# ATTinyAmpDriver.net
KiCad netlist of a schematic drawn in EAGLE
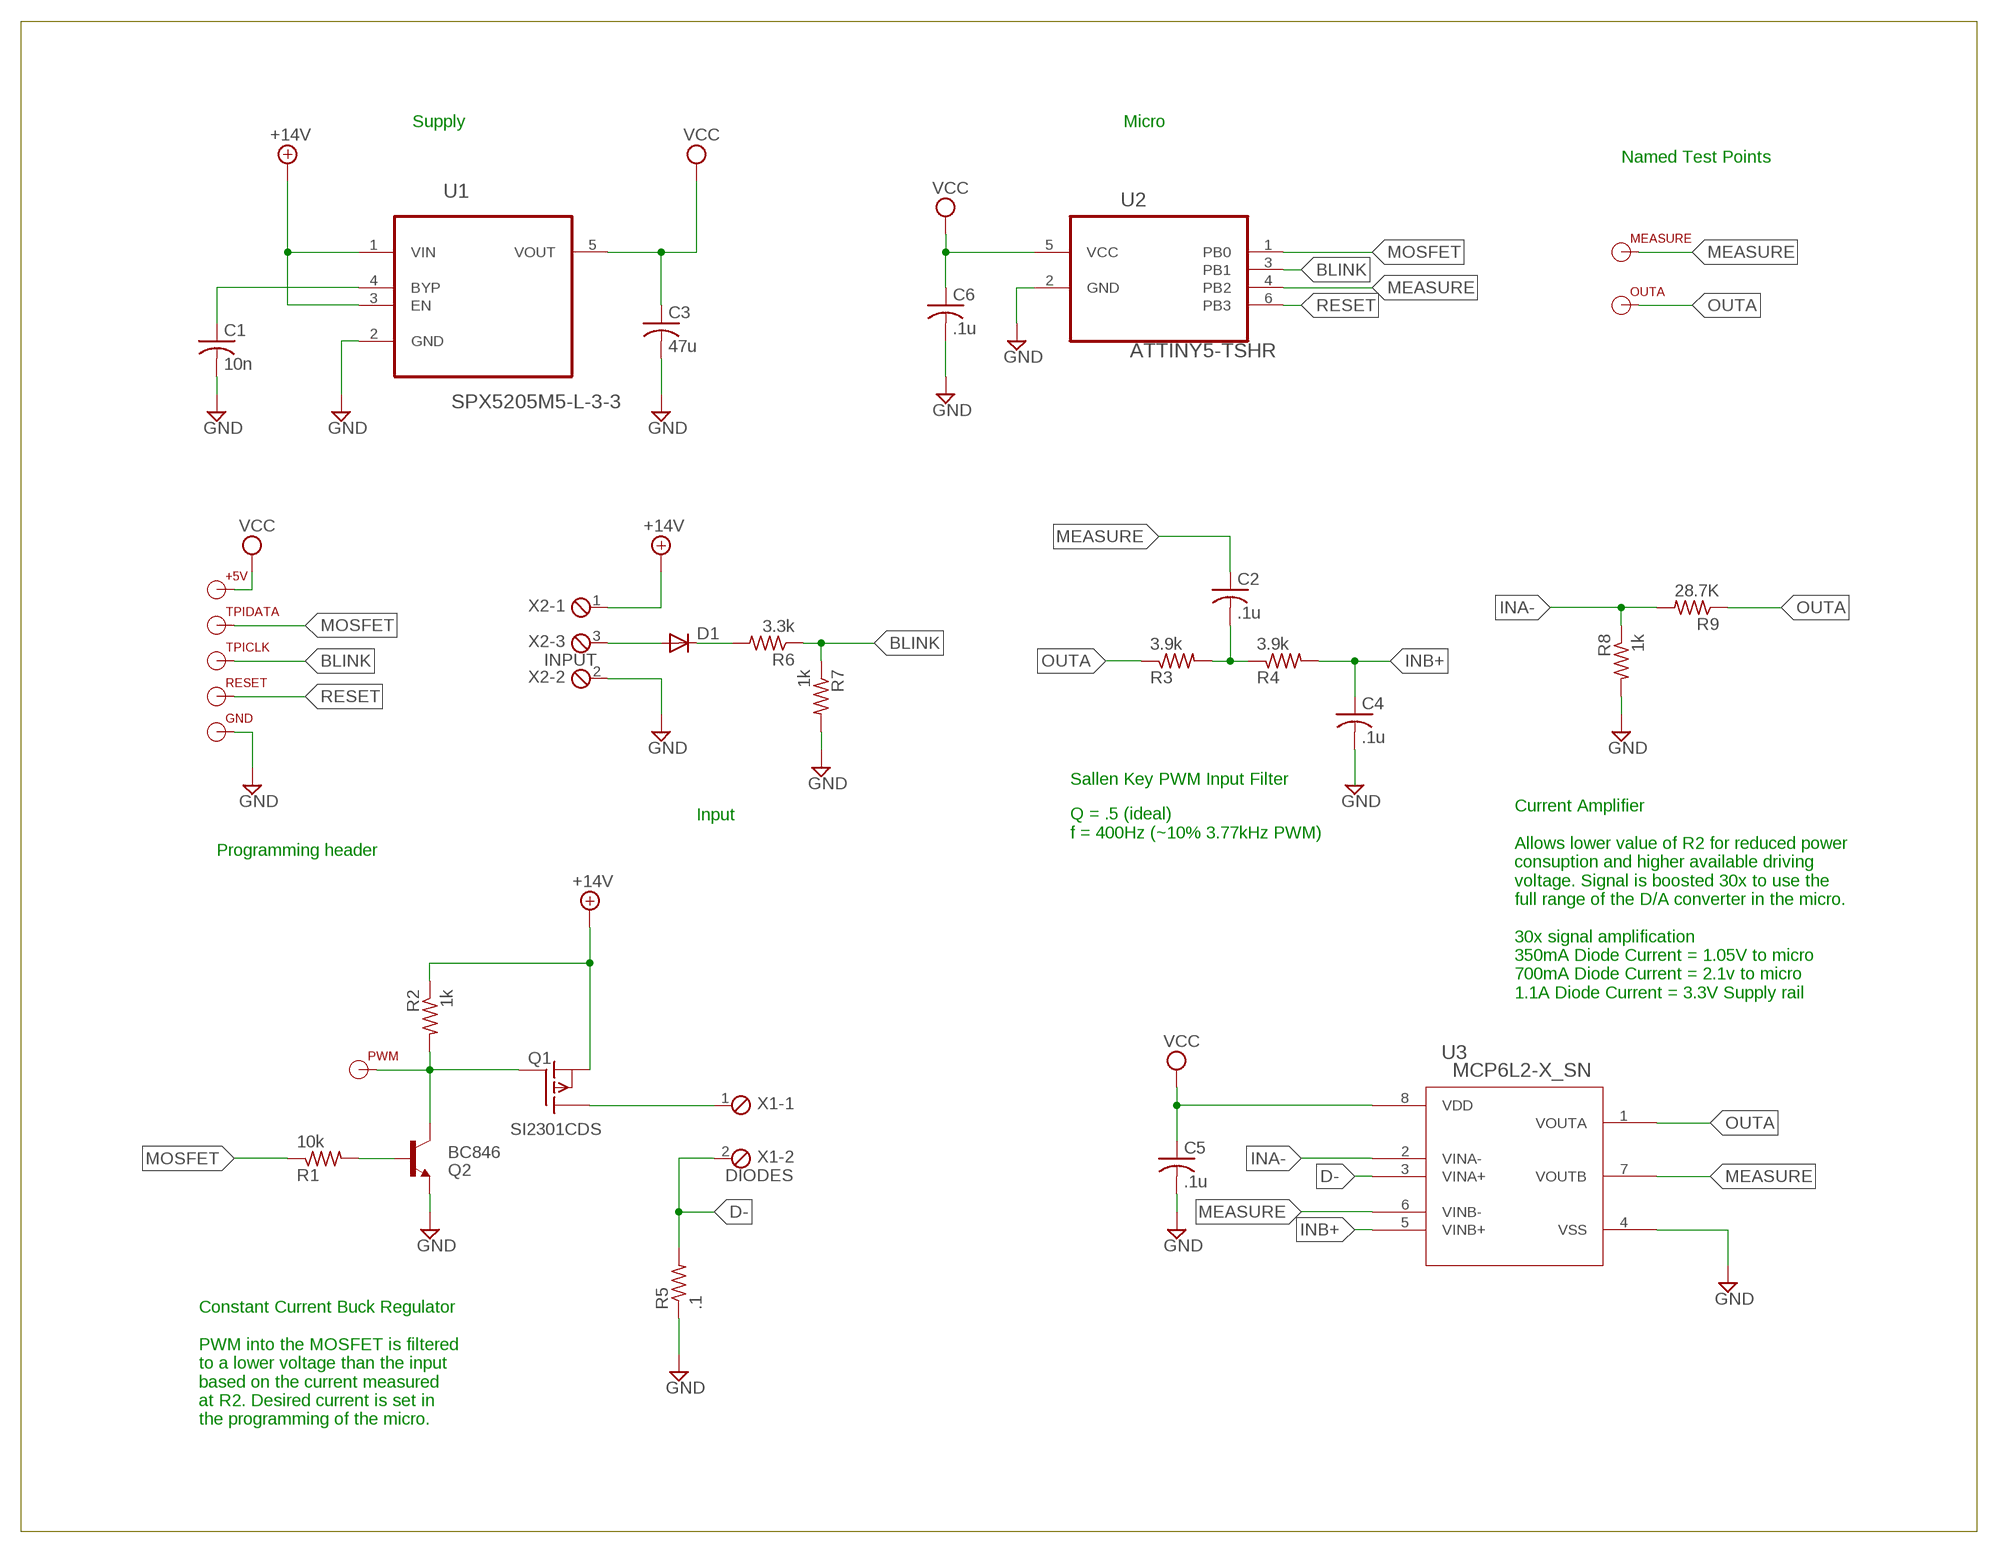
[diagram p0: schematic, sheet 1]

(export (version "E")
  (design (tool "Eeschema 10.0.6"))
  (components
    (comp (ref "+5V")
      (value "TPI")
      (footprint "eagle-import:TPI_PAD")
      (libsource (lib "eagle-import") (part "TPI"))
    )
    (comp (ref "C1")
      (value "10n")
      (footprint "eagle-import:C0603")
      (libsource (lib "eagle-import") (part "C-USC0603"))
    )
    (comp (ref "C2")
      (value ".1u")
      (footprint "eagle-import:C0603")
      (libsource (lib "eagle-import") (part "C-USC0603"))
    )
    (comp (ref "C3")
      (value "47u")
      (footprint "eagle-import:C1206")
      (libsource (lib "eagle-import") (part "C-USC1206"))
    )
    (comp (ref "C4")
      (value ".1u")
      (footprint "eagle-import:C0603")
      (libsource (lib "eagle-import") (part "C-USC0603"))
    )
    (comp (ref "C5")
      (value ".1u")
      (footprint "eagle-import:C0603")
      (libsource (lib "eagle-import") (part "C-USC0603"))
    )
    (comp (ref "C6")
      (value ".1u")
      (footprint "eagle-import:C0603")
      (libsource (lib "eagle-import") (part "C-USC0603"))
    )
    (comp (ref "D1")
      (value "DIODE_0603")
      (footprint "eagle-import:D0603")
      (libsource (lib "eagle-import") (part "DIODE_0603"))
    )
    (comp (ref "GND")
      (value "TPI")
      (footprint "eagle-import:TPI_PAD")
      (libsource (lib "eagle-import") (part "TPI"))
    )
    (comp (ref "MEASURE")
      (value "TPI")
      (footprint "eagle-import:TPI_PAD")
      (libsource (lib "eagle-import") (part "TPI"))
    )
    (comp (ref "OUTA")
      (value "TPI")
      (footprint "eagle-import:TPI_PAD")
      (libsource (lib "eagle-import") (part "TPI"))
    )
    (comp (ref "PWM")
      (value "TPI")
      (footprint "eagle-import:TPI_PAD")
      (libsource (lib "eagle-import") (part "TPI"))
    )
    (comp (ref "Q1")
      (value "SI2301CDS")
      (footprint "eagle-import:SOT-23_POWER")
      (libsource (lib "eagle-import") (part "SI2301CDS"))
    )
    (comp (ref "Q2")
      (value "BC846")
      (footprint "eagle-import:SOT23")
      (libsource (lib "eagle-import") (part "BC846"))
    )
    (comp (ref "R1")
      (value "10k")
      (footprint "eagle-import:R0603")
      (libsource (lib "eagle-import") (part "R-US_R0603"))
    )
    (comp (ref "R2")
      (value "1k")
      (footprint "eagle-import:R0603")
      (libsource (lib "eagle-import") (part "R-US_R0603"))
    )
    (comp (ref "R3")
      (value "3.9k")
      (footprint "eagle-import:R0603")
      (libsource (lib "eagle-import") (part "R-US_R0603"))
    )
    (comp (ref "R4")
      (value "3.9k")
      (footprint "eagle-import:R0603")
      (libsource (lib "eagle-import") (part "R-US_R0603"))
    )
    (comp (ref "R5")
      (value ".1")
      (footprint "eagle-import:R1206")
      (libsource (lib "eagle-import") (part "R-US_R1206"))
    )
    (comp (ref "R6")
      (value "3.3k")
      (footprint "eagle-import:R0603")
      (libsource (lib "eagle-import") (part "R-US_R0603"))
    )
    (comp (ref "R7")
      (value "1k")
      (footprint "eagle-import:R0603")
      (libsource (lib "eagle-import") (part "R-US_R0603"))
    )
    (comp (ref "R8")
      (value "1k")
      (footprint "eagle-import:R0603")
      (libsource (lib "eagle-import") (part "R-US_R0603"))
    )
    (comp (ref "R9")
      (value "28.7K")
      (footprint "eagle-import:R0603")
      (libsource (lib "eagle-import") (part "R-US_R0603"))
    )
    (comp (ref "RESET")
      (value "TPI")
      (footprint "eagle-import:TPI_PAD")
      (libsource (lib "eagle-import") (part "TPI"))
    )
    (comp (ref "TPICLK")
      (value "TPI")
      (footprint "eagle-import:TPI_PAD")
      (libsource (lib "eagle-import") (part "TPI"))
    )
    (comp (ref "TPIDATA")
      (value "TPI")
      (footprint "eagle-import:TPI_PAD")
      (libsource (lib "eagle-import") (part "TPI"))
    )
    (comp (ref "U1")
      (value "SPX5205M5-L-3-3")
      (footprint "eagle-import:SOT95P280X145-5N")
      (libsource (lib "eagle-import") (part "SPX5205M5-L-3-3"))
    )
    (comp (ref "U2")
      (value "ATTINY5-TSHR")
      (footprint "eagle-import:SOT95P280X145-6N")
      (libsource (lib "eagle-import") (part "ATTINY5-TSHR"))
    )
    (comp (ref "U3")
      (value "MCP6L2-X_SN")
      (footprint "eagle-import:SOIC8-N_MC")
      (libsource (lib "eagle-import") (part "MCP6L2-X_SN"))
    )
    (comp (ref "X1")
      (value "DIODES")
      (footprint "eagle-import:2POL254")
      (libsource (lib "eagle-import") (part "MPT2"))
    )
    (comp (ref "X2")
      (value "INPUT")
      (footprint "eagle-import:3POL254")
      (libsource (lib "eagle-import") (part "MPT3"))
    )
  )
  (nets
    (net (code "1") (name "+14V") (class "Default")
      (node (ref "Q1") (pin "P$2") (pinfunction "S_P$2") (pintype "passive"))
      (node (ref "R2") (pin "1") (pinfunction "1_1") (pintype "passive"))
      (node (ref "U1") (pin "1") (pinfunction "VIN_1") (pintype "power_in"))
      (node (ref "U1") (pin "3") (pinfunction "EN_3") (pintype "input"))
      (node (ref "X2") (pin "1") (pinfunction "1_1") (pintype "passive"))
    )
    (net (code "2") (name "BLINK") (class "Default")
      (node (ref "R6") (pin "1") (pinfunction "1_1") (pintype "passive"))
      (node (ref "R7") (pin "1") (pinfunction "1_1") (pintype "passive"))
      (node (ref "TPICLK") (pin "P$1") (pinfunction "TPI_PIN_P$1") (pintype "bidirectional"))
      (node (ref "U2") (pin "3") (pinfunction "PB1_3") (pintype "bidirectional"))
    )
    (net (code "3") (name "D-") (class "Default")
      (node (ref "R5") (pin "2") (pinfunction "2_2") (pintype "passive"))
      (node (ref "U3") (pin "3") (pinfunction "VINA+_3") (pintype "passive"))
      (node (ref "X1") (pin "2") (pinfunction "1_2") (pintype "passive"))
    )
    (net (code "4") (name "GND") (class "Default")
      (node (ref "C1") (pin "2") (pinfunction "2_2") (pintype "passive"))
      (node (ref "C3") (pin "2") (pinfunction "2_2") (pintype "passive"))
      (node (ref "C4") (pin "2") (pinfunction "2_2") (pintype "passive"))
      (node (ref "C5") (pin "2") (pinfunction "2_2") (pintype "passive"))
      (node (ref "C6") (pin "2") (pinfunction "2_2") (pintype "passive"))
      (node (ref "GND") (pin "P$1") (pinfunction "TPI_PIN_P$1") (pintype "bidirectional"))
      (node (ref "Q2") (pin "2") (pinfunction "E_2") (pintype "passive"))
      (node (ref "R5") (pin "1") (pinfunction "1_1") (pintype "passive"))
      (node (ref "R7") (pin "2") (pinfunction "2_2") (pintype "passive"))
      (node (ref "R8") (pin "2") (pinfunction "2_2") (pintype "passive"))
      (node (ref "U1") (pin "2") (pinfunction "GND_2") (pintype "passive"))
      (node (ref "U2") (pin "2") (pinfunction "GND_2") (pintype "passive"))
      (node (ref "U3") (pin "4") (pinfunction "VSS_4") (pintype "passive"))
      (node (ref "X2") (pin "2") (pinfunction "1_2") (pintype "passive"))
    )
    (net (code "5") (name "INA-") (class "Default")
      (node (ref "R8") (pin "1") (pinfunction "1_1") (pintype "passive"))
      (node (ref "R9") (pin "2") (pinfunction "2_2") (pintype "passive"))
      (node (ref "U3") (pin "2") (pinfunction "VINA-_2") (pintype "passive"))
    )
    (net (code "6") (name "INB+") (class "Default")
      (node (ref "C4") (pin "1") (pinfunction "1_1") (pintype "passive"))
      (node (ref "R4") (pin "2") (pinfunction "2_2") (pintype "passive"))
      (node (ref "U3") (pin "5") (pinfunction "VINB+_5") (pintype "passive"))
    )
    (net (code "7") (name "MEASURE") (class "Default")
      (node (ref "C2") (pin "1") (pinfunction "1_1") (pintype "passive"))
      (node (ref "MEASURE") (pin "P$1") (pinfunction "TPI_PIN_P$1") (pintype "bidirectional"))
      (node (ref "U2") (pin "4") (pinfunction "PB2_4") (pintype "bidirectional"))
      (node (ref "U3") (pin "6") (pinfunction "VINB-_6") (pintype "passive"))
      (node (ref "U3") (pin "7") (pinfunction "VOUTB_7") (pintype "passive"))
    )
    (net (code "8") (name "MOSFET") (class "Default")
      (node (ref "R1") (pin "1") (pinfunction "1_1") (pintype "passive"))
      (node (ref "TPIDATA") (pin "P$1") (pinfunction "TPI_PIN_P$1") (pintype "bidirectional"))
      (node (ref "U2") (pin "1") (pinfunction "PB0_1") (pintype "bidirectional"))
    )
    (net (code "9") (name "Net-(C2-Pad2)") (class "Default")
      (node (ref "C2") (pin "2") (pinfunction "2_2") (pintype "passive"))
      (node (ref "R3") (pin "2") (pinfunction "2_2") (pintype "passive"))
      (node (ref "R4") (pin "1") (pinfunction "1_1") (pintype "passive"))
    )
    (net (code "10") (name "Net-(D1-A)") (class "Default")
      (node (ref "D1") (pin "1A") (pinfunction "A_1A") (pintype "passive"))
      (node (ref "X2") (pin "3") (pinfunction "1_3") (pintype "passive"))
    )
    (net (code "11") (name "Net-(D1-C)") (class "Default")
      (node (ref "D1") (pin "2C") (pinfunction "C_2C") (pintype "passive"))
      (node (ref "R6") (pin "2") (pinfunction "2_2") (pintype "passive"))
    )
    (net (code "12") (name "Net-(PWM-TPI_PIN)") (class "Default")
      (node (ref "PWM") (pin "P$1") (pinfunction "TPI_PIN_P$1") (pintype "bidirectional"))
      (node (ref "Q1") (pin "P$1") (pinfunction "G_P$1") (pintype "passive"))
      (node (ref "Q2") (pin "3") (pinfunction "C_3") (pintype "passive"))
      (node (ref "R2") (pin "2") (pinfunction "2_2") (pintype "passive"))
    )
    (net (code "13") (name "Net-(Q1-D)") (class "Default")
      (node (ref "Q1") (pin "P$3") (pinfunction "D_P$3") (pintype "passive"))
      (node (ref "X1") (pin "1") (pinfunction "1_1") (pintype "passive"))
    )
    (net (code "14") (name "Net-(Q2-B)") (class "Default")
      (node (ref "Q2") (pin "1") (pinfunction "B_1") (pintype "passive"))
      (node (ref "R1") (pin "2") (pinfunction "2_2") (pintype "passive"))
    )
    (net (code "15") (name "Net-(U1-BYP)") (class "Default")
      (node (ref "C1") (pin "1") (pinfunction "1_1") (pintype "passive"))
      (node (ref "U1") (pin "4") (pinfunction "BYP_4") (pintype "input"))
    )
    (net (code "16") (name "OUTA") (class "Default")
      (node (ref "OUTA") (pin "P$1") (pinfunction "TPI_PIN_P$1") (pintype "bidirectional"))
      (node (ref "R3") (pin "1") (pinfunction "1_1") (pintype "passive"))
      (node (ref "R9") (pin "1") (pinfunction "1_1") (pintype "passive"))
      (node (ref "U3") (pin "1") (pinfunction "VOUTA_1") (pintype "passive"))
    )
    (net (code "17") (name "RESET") (class "Default")
      (node (ref "RESET") (pin "P$1") (pinfunction "TPI_PIN_P$1") (pintype "bidirectional"))
      (node (ref "U2") (pin "6") (pinfunction "PB3_6") (pintype "bidirectional"))
    )
    (net (code "18") (name "VCC") (class "Default")
      (node (ref "+5V") (pin "P$1") (pinfunction "TPI_PIN_P$1") (pintype "bidirectional"))
      (node (ref "C3") (pin "1") (pinfunction "1_1") (pintype "passive"))
      (node (ref "C5") (pin "1") (pinfunction "1_1") (pintype "passive"))
      (node (ref "C6") (pin "1") (pinfunction "1_1") (pintype "passive"))
      (node (ref "U1") (pin "5") (pinfunction "VOUT_5") (pintype "output"))
      (node (ref "U2") (pin "5") (pinfunction "VCC_5") (pintype "power_in"))
      (node (ref "U3") (pin "8") (pinfunction "VDD_8") (pintype "passive"))
    )
  )
)
